# Voltage_Measurment.net
KiCad netlist of a schematic drawn in Altium Designer
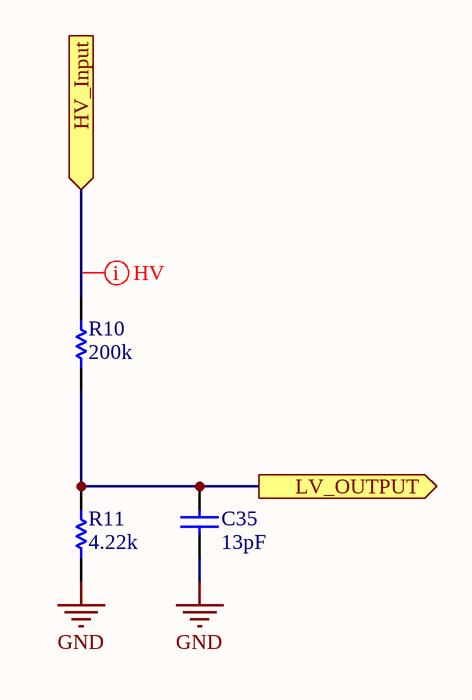
[diagram p0: Voltage_Measurment.SchDoc]

(export (version "E")
  (design (tool "Eeschema 10.0.6"))
  (components
    (comp (ref "C35")
      (value "13pF")
      (footprint "0603_CAPACITOR")
      (fields (field (name "TOLERANCE") "5%") (field (name "Comment") "Capacitor 13pF 0603 5% 50V"))
      (libsource (lib "University of Minnesota - Solar Vehicle Project") (part "Cap"))
    )
    (comp (ref "R10")
      (value "200k")
      (footprint "1206_RESISTOR")
      (description "Resistor 200K 1206 1% 1/4W")
      (fields (field (name "TOLERANCE") "1%") (field (name "POWER") "250mW"))
      (libsource (lib "University of Minnesota - Solar Vehicle Project") (part "RES-2"))
    )
    (comp (ref "R11")
      (value "4.22k")
      (footprint "0603_RESISTOR")
      (fields
        (field (name "TOLERANCE") "1%")
        (field (name "POWER") "100mW")
        (field (name "Comment") "Resistor 4.22k 0603 0.1W 1%")
      )
      (libsource (lib "University of Minnesota - Solar Vehicle Project") (part "RES-2"))
    )
  )
  (nets
    (net (code "1") (name "/HV_Input") (class "Default")
      (node (ref "R10") (pin "2") (pinfunction "2_2") (pintype "passive"))
    )
    (net (code "2") (name "/LV_OUTPUT") (class "Default")
      (node (ref "C35") (pin "2") (pinfunction "2_2") (pintype "passive"))
      (node (ref "R10") (pin "1") (pinfunction "1_1") (pintype "passive"))
      (node (ref "R11") (pin "2") (pinfunction "2_2") (pintype "passive"))
    )
    (net (code "3") (name "GND") (class "Default")
      (node (ref "C35") (pin "1") (pinfunction "1_1") (pintype "passive"))
      (node (ref "R11") (pin "1") (pinfunction "1_1") (pintype "passive"))
    )
  )
)
